# ASCII_06_LMS7002M_RF2.net
KiCad netlist of a schematic drawn in Altium Designer
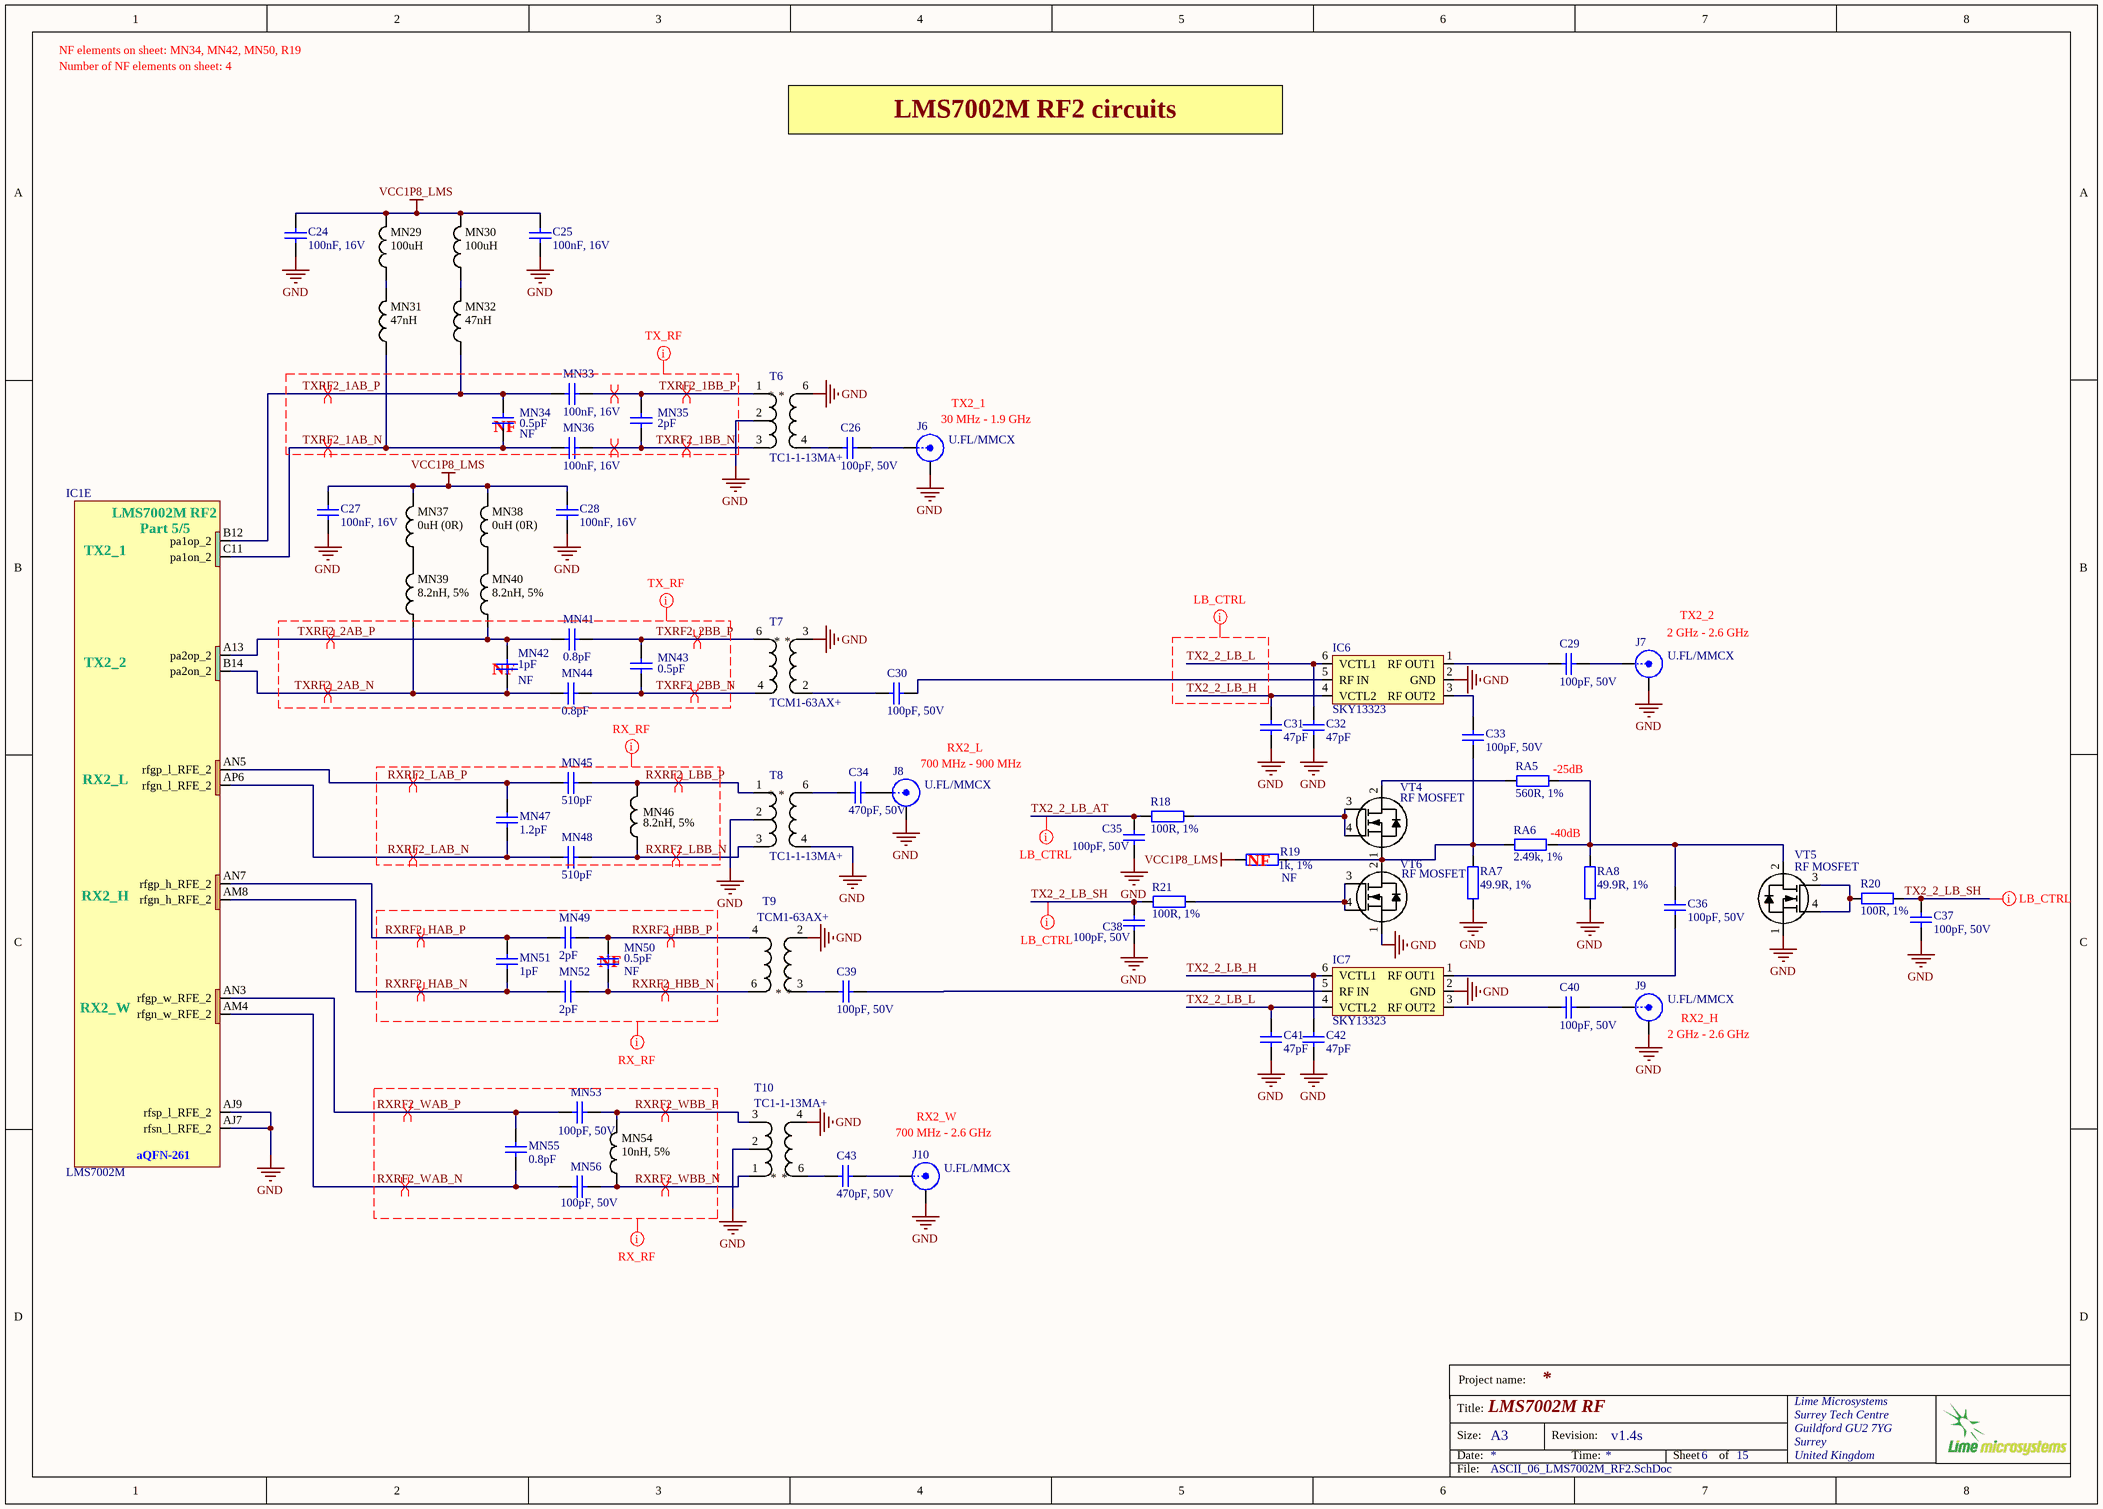
[diagram p0: ASCII_06_LMS7002M_RF2.SchDoc]

(export (version "E")
  (design (tool "Eeschema 10.0.6"))
  (components
    (comp (ref "C24")
      (value "100nF, 16V")
      (footprint "CAP0402")
      (fields
        (field (name "MANUFACTURER") "Murata Electronics")
        (field (name "TOLERANCE") "10 %")
        (field (name "MANUFACTURER PART NUMBER") "GRM155R71C104KA88D")
      )
      (libsource (lib "LimeMicroAltiumLib_schLib") (part "Cap_0402"))
    )
    (comp (ref "C25")
      (value "100nF, 16V")
      (footprint "CAP0402")
      (fields
        (field (name "MANUFACTURER") "Murata Electronics")
        (field (name "TOLERANCE") "10 %")
        (field (name "MANUFACTURER PART NUMBER") "GRM155R71C104KA88D")
      )
      (libsource (lib "LimeMicroAltiumLib_schLib") (part "Cap_0402"))
    )
    (comp (ref "C26")
      (value "100pF, 50V")
      (footprint "CAP0402")
      (fields (field (name "TOLERANCE") "±5%") (field (name "MANUFACTURER") "Yageo"))
      (libsource (lib "LimeMicroAltiumLib_schLib") (part "Cap_0402"))
    )
    (comp (ref "C27")
      (value "100nF, 16V")
      (footprint "CAP0402")
      (fields
        (field (name "MANUFACTURER") "Murata Electronics")
        (field (name "TOLERANCE") "10 %")
        (field (name "MANUFACTURER PART NUMBER") "GRM155R71C104KA88D")
      )
      (libsource (lib "LimeMicroAltiumLib_schLib") (part "Cap_0402"))
    )
    (comp (ref "C28")
      (value "100nF, 16V")
      (footprint "CAP0402")
      (fields
        (field (name "MANUFACTURER") "Murata Electronics")
        (field (name "TOLERANCE") "10 %")
        (field (name "MANUFACTURER PART NUMBER") "GRM155R71C104KA88D")
      )
      (libsource (lib "LimeMicroAltiumLib_schLib") (part "Cap_0402"))
    )
    (comp (ref "C29")
      (value "100pF, 50V")
      (footprint "CAP0402")
      (fields (field (name "TOLERANCE") "±5%") (field (name "MANUFACTURER") "Yageo"))
      (libsource (lib "LimeMicroAltiumLib_schLib") (part "Cap_0402"))
    )
    (comp (ref "C30")
      (value "100pF, 50V")
      (footprint "CAP0402")
      (fields (field (name "TOLERANCE") "±5%") (field (name "MANUFACTURER") "Yageo"))
      (libsource (lib "LimeMicroAltiumLib_schLib") (part "Cap_0402"))
    )
    (comp (ref "C31")
      (value "47pF")
      (footprint "CAP0402")
      (fields (field (name "TOLERANCE") "±1%") (field (name "MANUFACTURER") "TDK Corporation"))
      (libsource (lib "LimeMicroAltiumLib_schLib") (part "Cap_0402"))
    )
    (comp (ref "C32")
      (value "47pF")
      (footprint "CAP0402")
      (fields (field (name "TOLERANCE") "±1%") (field (name "MANUFACTURER") "TDK Corporation"))
      (libsource (lib "LimeMicroAltiumLib_schLib") (part "Cap_0402"))
    )
    (comp (ref "C33")
      (value "100pF, 50V")
      (footprint "CAP0402")
      (fields (field (name "TOLERANCE") "±5%") (field (name "MANUFACTURER") "Yageo"))
      (libsource (lib "LimeMicroAltiumLib_schLib") (part "Cap_0402"))
    )
    (comp (ref "C34")
      (value "470pF, 50V")
      (footprint "CAP0402")
      (fields
        (field (name "MANUFACTURER PART NUMBER") "C1005C0G1H471J050BA")
        (field (name "TOLERANCE") "±5%")
        (field (name "MANUFACTURER") "TDK Corporation")
      )
      (libsource (lib "LimeMicroAltiumLib_schLib") (part "Cap_0402"))
    )
    (comp (ref "C35")
      (value "100pF, 50V")
      (footprint "CAP0402")
      (fields (field (name "TOLERANCE") "±5%") (field (name "MANUFACTURER") "Yageo"))
      (libsource (lib "LimeMicroAltiumLib_schLib") (part "Cap_0402"))
    )
    (comp (ref "C36")
      (value "100pF, 50V")
      (footprint "CAP0402")
      (fields (field (name "TOLERANCE") "±5%") (field (name "MANUFACTURER") "Yageo"))
      (libsource (lib "LimeMicroAltiumLib_schLib") (part "Cap_0402"))
    )
    (comp (ref "C37")
      (value "100pF, 50V")
      (footprint "CAP0402")
      (fields (field (name "TOLERANCE") "±5%") (field (name "MANUFACTURER") "Yageo"))
      (libsource (lib "LimeMicroAltiumLib_schLib") (part "Cap_0402"))
    )
    (comp (ref "C38")
      (value "100pF, 50V")
      (footprint "CAP0402")
      (fields (field (name "TOLERANCE") "±5%") (field (name "MANUFACTURER") "Yageo"))
      (libsource (lib "LimeMicroAltiumLib_schLib") (part "Cap_0402"))
    )
    (comp (ref "C39")
      (value "100pF, 50V")
      (footprint "CAP0402")
      (fields (field (name "TOLERANCE") "±5%") (field (name "MANUFACTURER") "Yageo"))
      (libsource (lib "LimeMicroAltiumLib_schLib") (part "Cap_0402"))
    )
    (comp (ref "C40")
      (value "100pF, 50V")
      (footprint "CAP0402")
      (fields (field (name "TOLERANCE") "±5%") (field (name "MANUFACTURER") "Yageo"))
      (libsource (lib "LimeMicroAltiumLib_schLib") (part "Cap_0402"))
    )
    (comp (ref "C41")
      (value "47pF")
      (footprint "CAP0402")
      (fields (field (name "TOLERANCE") "±1%") (field (name "MANUFACTURER") "TDK Corporation"))
      (libsource (lib "LimeMicroAltiumLib_schLib") (part "Cap_0402"))
    )
    (comp (ref "C42")
      (value "47pF")
      (footprint "CAP0402")
      (fields (field (name "TOLERANCE") "±1%") (field (name "MANUFACTURER") "TDK Corporation"))
      (libsource (lib "LimeMicroAltiumLib_schLib") (part "Cap_0402"))
    )
    (comp (ref "C43")
      (value "470pF, 50V")
      (footprint "CAP0402")
      (fields
        (field (name "MANUFACTURER PART NUMBER") "C1005C0G1H471J050BA")
        (field (name "TOLERANCE") "±5%")
        (field (name "MANUFACTURER") "TDK Corporation")
      )
      (libsource (lib "LimeMicroAltiumLib_schLib") (part "Cap_0402"))
    )
    (comp (ref "IC1")
      (value "LMS7002M")
      (footprint "LMS7002M_v3")
      (fields (field (name "MANUFACTURER") "Lime Microsystems"))
      (libsource (lib "LimeMicroAltiumLib_schLib") (part "LMS7002M"))
    )
    (comp (ref "IC6")
      (value "SKY13323")
      (footprint "SKY13323-378LF")
      (description "SKY13323-378LF: 0.1-3.0 GHz GaAs SPDT Switch")
      (fields (field (name "MANUFACTURER") "Skyworks Solutions Inc."))
      (libsource (lib "LimeMicroAltiumLib_schLib") (part "SKY13323"))
    )
    (comp (ref "IC7")
      (value "SKY13323")
      (footprint "SKY13323-378LF")
      (description "SKY13323-378LF: 0.1-3.0 GHz GaAs SPDT Switch")
      (fields (field (name "MANUFACTURER") "Skyworks Solutions Inc."))
      (libsource (lib "LimeMicroAltiumLib_schLib") (part "SKY13323"))
    )
    (comp (ref "J6")
      (value "U.FL/MMCX")
      (footprint "MMCX_UFL_conn_u")
      (description "CONN UMC RCPT STR 50 OHM SMD")
      (fields (field (name "MANUFACTURER") "Molex, LLC"))
      (libsource (lib "LimeMicroAltiumLib_schLib") (part "RF_IF_connector"))
    )
    (comp (ref "J7")
      (value "U.FL/MMCX")
      (footprint "MMCX_UFL_conn_u")
      (description "CONN UMC RCPT STR 50 OHM SMD")
      (fields (field (name "MANUFACTURER") "Molex, LLC"))
      (libsource (lib "LimeMicroAltiumLib_schLib") (part "RF_IF_connector"))
    )
    (comp (ref "J8")
      (value "U.FL/MMCX")
      (footprint "MMCX_UFL_conn_u")
      (description "CONN UMC RCPT STR 50 OHM SMD")
      (fields (field (name "MANUFACTURER") "Molex, LLC"))
      (libsource (lib "LimeMicroAltiumLib_schLib") (part "RF_IF_connector"))
    )
    (comp (ref "J9")
      (value "U.FL/MMCX")
      (footprint "MMCX_UFL_conn_u")
      (description "CONN UMC RCPT STR 50 OHM SMD")
      (fields (field (name "MANUFACTURER") "Molex, LLC"))
      (libsource (lib "LimeMicroAltiumLib_schLib") (part "RF_IF_connector"))
    )
    (comp (ref "J10")
      (value "U.FL/MMCX")
      (footprint "MMCX_UFL_conn_u")
      (description "CONN UMC RCPT STR 50 OHM SMD")
      (fields (field (name "MANUFACTURER") "Molex, LLC"))
      (libsource (lib "LimeMicroAltiumLib_schLib") (part "RF_IF_connector"))
    )
    (comp (ref "MN29")
      (value "100uH")
      (footprint "RES0805")
      (fields
        (field (name "TOLERANCE") "±10%")
        (field (name "MANUFACTURER") "TDK Corporation")
        (field (name "MANUFACTURER PART NUMBER") "MLF2012C101KT000")
      )
      (libsource (lib "LimeMicroAltiumLib_schLib") (part "Inductor_0603"))
    )
    (comp (ref "MN30")
      (value "100uH")
      (footprint "RES0805")
      (fields
        (field (name "TOLERANCE") "±10%")
        (field (name "MANUFACTURER") "TDK Corporation")
        (field (name "MANUFACTURER PART NUMBER") "MLF2012C101KT000")
      )
      (libsource (lib "LimeMicroAltiumLib_schLib") (part "Inductor_0603"))
    )
    (comp (ref "MN31")
      (value "47nH")
      (footprint "RES0402")
      (fields
        (field (name "MANUFACTURER") "COILCRAFT")
        (field (name "MANUFACTURER PART NUMBER") "0402HP-47NXJLU")
      )
      (libsource (lib "LimeMicroAltiumLib_schLib") (part "Inductor_0603"))
    )
    (comp (ref "MN32")
      (value "47nH")
      (footprint "RES0402")
      (fields
        (field (name "MANUFACTURER") "COILCRAFT")
        (field (name "MANUFACTURER PART NUMBER") "0402HP-47NXJLU")
      )
      (libsource (lib "LimeMicroAltiumLib_schLib") (part "Inductor_0603"))
    )
    (comp (ref "MN33")
      (value "100nF, 16V")
      (footprint "CAP0402")
      (fields
        (field (name "MANUFACTURER") "Murata Electronics")
        (field (name "TOLERANCE") "10 %")
        (field (name "MANUFACTURER PART NUMBER") "GRM155R71C104KA88D")
      )
      (libsource (lib "LimeMicroAltiumLib_schLib") (part "Cap_0402"))
    )
    (comp (ref "MN34")
      (value "0.5pF")
      (footprint "CAP0402")
      (fields
        (field (name "ASSEMBLY INFO") "NF")
        (field (name "TOLERANCE") "±0.25pF")
        (field (name "MANUFACTURER") "Yageo")
      )
      (libsource (lib "LimeMicroAltiumLib_schLib") (part "Cap_0402"))
    )
    (comp (ref "MN35")
      (value "2pF")
      (footprint "CAP0402")
      (fields (field (name "MANUFACTURER PART NUMBER") "04025U2R0BAT2A") (field (name "MANUFACTURER") "AVX"))
      (libsource (lib "LimeMicroAltiumLib_schLib") (part "Cap_0402"))
    )
    (comp (ref "MN36")
      (value "100nF, 16V")
      (footprint "CAP0402")
      (fields
        (field (name "MANUFACTURER") "Murata Electronics")
        (field (name "TOLERANCE") "10 %")
        (field (name "MANUFACTURER PART NUMBER") "GRM155R71C104KA88D")
      )
      (libsource (lib "LimeMicroAltiumLib_schLib") (part "Cap_0402"))
    )
    (comp (ref "MN37")
      (value "0uH (0R)")
      (footprint "RES0805")
      (fields (field (name "MANUFACTURER") "BOURNS"))
      (libsource (lib "LimeMicroAltiumLib_schLib") (part "Inductor_0603"))
    )
    (comp (ref "MN38")
      (value "0uH (0R)")
      (footprint "RES0805")
      (fields (field (name "MANUFACTURER") "BOURNS"))
      (libsource (lib "LimeMicroAltiumLib_schLib") (part "Inductor_0603"))
    )
    (comp (ref "MN39")
      (value "8.2nH, 5%")
      (footprint "RES0402")
      (fields (field (name "MANUFACTURER") "COILCRAFT"))
      (libsource (lib "LimeMicroAltiumLib_schLib") (part "Inductor_0603"))
    )
    (comp (ref "MN40")
      (value "8.2nH, 5%")
      (footprint "RES0402")
      (fields (field (name "MANUFACTURER") "COILCRAFT"))
      (libsource (lib "LimeMicroAltiumLib_schLib") (part "Inductor_0603"))
    )
    (comp (ref "MN41")
      (value "0.8pF")
      (footprint "CAP0402")
      (fields
        (field (name "TOLERANCE") "±0.1pF")
        (field (name "MANUFACTURER") "Murata Electronics North America")
        (field (name "MANUFACTURER PART NUMBER") "GRM1555C1HR80BA01D")
      )
      (libsource (lib "LimeMicroAltiumLib_schLib") (part "Cap_0402"))
    )
    (comp (ref "MN42")
      (value "1pF")
      (footprint "CAP0402")
      (fields
        (field (name "ASSEMBLY INFO") "NF")
        (field (name "MANUFACTURER") "TDK Corporation")
        (field (name "TOLERANCE") "±0.1pF")
      )
      (libsource (lib "LimeMicroAltiumLib_schLib") (part "Cap_0402"))
    )
    (comp (ref "MN43")
      (value "0.5pF")
      (footprint "CAP0402")
      (fields (field (name "TOLERANCE") "±0.25pF") (field (name "MANUFACTURER") "Yageo"))
      (libsource (lib "LimeMicroAltiumLib_schLib") (part "Cap_0402"))
    )
    (comp (ref "MN44")
      (value "0.8pF")
      (footprint "CAP0402")
      (fields
        (field (name "TOLERANCE") "±0.1pF")
        (field (name "MANUFACTURER") "Murata Electronics North America")
        (field (name "MANUFACTURER PART NUMBER") "GRM1555C1HR80BA01D")
      )
      (libsource (lib "LimeMicroAltiumLib_schLib") (part "Cap_0402"))
    )
    (comp (ref "MN45")
      (value "510pF")
      (footprint "CAP0402")
      (fields
        (field (name "TOLERANCE") "±5%")
        (field (name "MANUFACTURER") "Murata Electronics North America")
        (field (name "MANUFACTURER PART NUMBER") "GRM1555C1H511JA01D")
      )
      (libsource (lib "LimeMicroAltiumLib_schLib") (part "Cap_0402"))
    )
    (comp (ref "MN46")
      (value "8.2nH, 5%")
      (footprint "RES0402")
      (fields (field (name "MANUFACTURER") "COILCRAFT"))
      (libsource (lib "LimeMicroAltiumLib_schLib") (part "Inductor_0603"))
    )
    (comp (ref "MN47")
      (value "1.2pF")
      (footprint "CAP0402")
      (fields
        (field (name "MANUFACTURER") "Murata Electronics North America")
        (field (name "MANUFACTURER PART NUMBER") "GRM1555C1H1R2CA01D")
        (field (name "TOLERANCE") "±0.25pF")
      )
      (libsource (lib "LimeMicroAltiumLib_schLib") (part "Cap_0402"))
    )
    (comp (ref "MN48")
      (value "510pF")
      (footprint "CAP0402")
      (fields
        (field (name "TOLERANCE") "±5%")
        (field (name "MANUFACTURER") "Murata Electronics North America")
        (field (name "MANUFACTURER PART NUMBER") "GRM1555C1H511JA01D")
      )
      (libsource (lib "LimeMicroAltiumLib_schLib") (part "Cap_0402"))
    )
    (comp (ref "MN49")
      (value "2pF")
      (footprint "CAP0402")
      (fields (field (name "MANUFACTURER PART NUMBER") "04025U2R0BAT2A") (field (name "MANUFACTURER") "AVX"))
      (libsource (lib "LimeMicroAltiumLib_schLib") (part "Cap_0402"))
    )
    (comp (ref "MN50")
      (value "0.5pF")
      (footprint "CAP0402")
      (fields
        (field (name "ASSEMBLY INFO") "NF")
        (field (name "TOLERANCE") "±0.25pF")
        (field (name "MANUFACTURER") "Yageo")
      )
      (libsource (lib "LimeMicroAltiumLib_schLib") (part "Cap_0402"))
    )
    (comp (ref "MN51")
      (value "1pF")
      (footprint "CAP0402")
      (fields (field (name "MANUFACTURER") "TDK Corporation") (field (name "TOLERANCE") "±0.1pF"))
      (libsource (lib "LimeMicroAltiumLib_schLib") (part "Cap_0402"))
    )
    (comp (ref "MN52")
      (value "2pF")
      (footprint "CAP0402")
      (fields (field (name "MANUFACTURER PART NUMBER") "04025U2R0BAT2A") (field (name "MANUFACTURER") "AVX"))
      (libsource (lib "LimeMicroAltiumLib_schLib") (part "Cap_0402"))
    )
    (comp (ref "MN53")
      (value "100pF, 50V")
      (footprint "CAP0402")
      (fields (field (name "TOLERANCE") "±5%") (field (name "MANUFACTURER") "Yageo"))
      (libsource (lib "LimeMicroAltiumLib_schLib") (part "Cap_0402"))
    )
    (comp (ref "MN54")
      (value "10nH, 5%")
      (footprint "RES0402")
      (fields (field (name "MANUFACTURER") "COILCRAFT"))
      (libsource (lib "LimeMicroAltiumLib_schLib") (part "Inductor_0603"))
    )
    (comp (ref "MN55")
      (value "0.8pF")
      (footprint "CAP0402")
      (fields
        (field (name "TOLERANCE") "±0.1pF")
        (field (name "MANUFACTURER") "Murata Electronics North America")
        (field (name "MANUFACTURER PART NUMBER") "GRM1555C1HR80BA01D")
      )
      (libsource (lib "LimeMicroAltiumLib_schLib") (part "Cap_0402"))
    )
    (comp (ref "MN56")
      (value "100pF, 50V")
      (footprint "CAP0402")
      (fields (field (name "TOLERANCE") "±5%") (field (name "MANUFACTURER") "Yageo"))
      (libsource (lib "LimeMicroAltiumLib_schLib") (part "Cap_0402"))
    )
    (comp (ref "R18")
      (value "100R, 1%")
      (footprint "RES0402")
      (fields (field (name "TOLERANCE") "±1%") (field (name "MANUFACTURER") "Stackpole Electronics Inc."))
      (libsource (lib "LimeFPGAboard_schLib") (part "Res_0402"))
    )
    (comp (ref "R19")
      (value "1k, 1%")
      (footprint "RES0402")
      (fields
        (field (name "ASSEMBLY INFO") "NF")
        (field (name "MANUFACTURER") "Stackpole Electronics Inc")
        (field (name "TOLERANCE") "±1%")
      )
      (libsource (lib "LimeMicroAltiumLib_schLib") (part "Res_0402"))
    )
    (comp (ref "R20")
      (value "100R, 1%")
      (footprint "RES0402")
      (fields (field (name "TOLERANCE") "±1%") (field (name "MANUFACTURER") "Stackpole Electronics Inc."))
      (libsource (lib "LimeFPGAboard_schLib") (part "Res_0402"))
    )
    (comp (ref "R21")
      (value "100R, 1%")
      (footprint "RES0402")
      (fields (field (name "TOLERANCE") "±1%") (field (name "MANUFACTURER") "Stackpole Electronics Inc."))
      (libsource (lib "LimeFPGAboard_schLib") (part "Res_0402"))
    )
    (comp (ref "RA5")
      (value "560R, 1%")
      (footprint "RES0402")
      (fields
        (field (name "MANUFACTURER PART NUMBER") "CRCW0402560RFKED")
        (field (name "TOLERANCE") "±1%")
        (field (name "MANUFACTURER") "Vishay Dale")
      )
      (libsource (lib "LimeMicroAltiumLib_schLib") (part "Res_0402"))
    )
    (comp (ref "RA6")
      (value "2.49k, 1%")
      (footprint "RES0402")
      (fields
        (field (name "TOLERANCE") "±1%")
        (field (name "MANUFACTURER PART NUMBER") "RC0402FR-072K49L")
        (field (name "MANUFACTURER") "Yageo")
      )
      (libsource (lib "LimeMicroAltiumLib_schLib") (part "Res_0402"))
    )
    (comp (ref "RA7")
      (value "49.9R, 1%")
      (footprint "RES0402")
      (fields
        (field (name "TOLERANCE") "±1%")
        (field (name "MANUFACTURER") "Samsung Electro-Mechanics America, Inc.")
        (field (name "MANUFACTURER PART NUMBER") "RC1005F49R9CS")
      )
      (libsource (lib "LimeMicroAltiumLib_schLib") (part "Res_0402"))
    )
    (comp (ref "RA8")
      (value "49.9R, 1%")
      (footprint "RES0402")
      (fields
        (field (name "TOLERANCE") "±1%")
        (field (name "MANUFACTURER") "Samsung Electro-Mechanics America, Inc.")
        (field (name "MANUFACTURER PART NUMBER") "RC1005F49R9CS")
      )
      (libsource (lib "LimeMicroAltiumLib_schLib") (part "Res_0402"))
    )
    (comp (ref "T6")
      (value "TC1-1-13MA+")
      (footprint "TC1-1-13MA+_v2")
      (fields (field (name "MANUFACTURER") "Mini-Circuits"))
      (libsource (lib "LimeMicroAltiumLib_schLib") (part "Balun"))
    )
    (comp (ref "T7")
      (value "TCM1-63AX+")
      (footprint "TCM1-63AX+_v2")
      (fields (field (name "MANUFACTURER") "Mini-circuits"))
      (libsource (lib "") (part "Balun_v2_1"))
    )
    (comp (ref "T8")
      (value "TC1-1-13MA+")
      (footprint "TC1-1-13MA+_v2")
      (fields (field (name "MANUFACTURER") "Mini-Circuits"))
      (libsource (lib "LimeMicroAltiumLib_schLib") (part "Balun"))
    )
    (comp (ref "T9")
      (value "TCM1-63AX+")
      (footprint "TCM1-63AX+_v2")
      (fields (field (name "MANUFACTURER") "Mini-circuits"))
      (libsource (lib "LimeMicroAltiumLib_schLib") (part "Balun_v2"))
    )
    (comp (ref "T10")
      (value "TC1-1-13MA+")
      (footprint "TC1-1-13MA+_v2")
      (fields (field (name "MANUFACTURER") "Mini-Circuits"))
      (libsource (lib "") (part "Balun_1"))
    )
    (comp (ref "VT4")
      (value "RF MOSFET")
      (footprint "BF1105R_SOT143R4")
      (fields (field (name "MANUFACTURER") "NXP Semiconductors"))
      (libsource (lib "LimeMicroAltiumLib_schLib") (part "BF1105R,215"))
    )
    (comp (ref "VT5")
      (value "RF MOSFET")
      (footprint "BF1105R_SOT143R4")
      (fields (field (name "MANUFACTURER") "NXP Semiconductors"))
      (libsource (lib "LimeMicroAltiumLib_schLib") (part "BF1105R,215"))
    )
    (comp (ref "VT6")
      (value "RF MOSFET")
      (footprint "BF1105R_SOT143R4")
      (fields (field (name "MANUFACTURER") "NXP Semiconductors"))
      (libsource (lib "LimeMicroAltiumLib_schLib") (part "BF1105R,215"))
    )
  )
  (nets
    (net (code "1") (name "/RXRF2_HAB_N") (class "Default")
      (node (ref "IC1") (pin "AM8") (pinfunction "rfgn_h_RFE_2_AM8") (pintype "passive"))
      (node (ref "MN51") (pin "1") (pinfunction "1_1") (pintype "passive"))
      (node (ref "MN52") (pin "2") (pinfunction "2_2") (pintype "passive"))
    )
    (net (code "2") (name "/RXRF2_HAB_P") (class "Default")
      (node (ref "IC1") (pin "AN7") (pinfunction "rfgp_h_RFE_2_AN7") (pintype "passive"))
      (node (ref "MN49") (pin "2") (pinfunction "2_2") (pintype "passive"))
      (node (ref "MN51") (pin "2") (pinfunction "2_2") (pintype "passive"))
    )
    (net (code "3") (name "/RXRF2_HBB_N") (class "Default")
      (node (ref "MN50") (pin "1") (pinfunction "1_1") (pintype "passive"))
      (node (ref "MN52") (pin "1") (pinfunction "1_1") (pintype "passive"))
      (node (ref "T9") (pin "6") (pinfunction "6_6") (pintype "passive"))
    )
    (net (code "4") (name "/RXRF2_HBB_P") (class "Default")
      (node (ref "MN49") (pin "1") (pinfunction "1_1") (pintype "passive"))
      (node (ref "MN50") (pin "2") (pinfunction "2_2") (pintype "passive"))
      (node (ref "T9") (pin "4") (pinfunction "4_4") (pintype "passive"))
    )
    (net (code "5") (name "/RXRF2_LAB_N") (class "Default")
      (node (ref "IC1") (pin "AP6") (pinfunction "rfgn_l_RFE_2_AP6") (pintype "passive"))
      (node (ref "MN47") (pin "1") (pinfunction "1_1") (pintype "passive"))
      (node (ref "MN48") (pin "2") (pinfunction "2_2") (pintype "passive"))
    )
    (net (code "6") (name "/RXRF2_LAB_P") (class "Default")
      (node (ref "IC1") (pin "AN5") (pinfunction "rfgp_l_RFE_2_AN5") (pintype "passive"))
      (node (ref "MN45") (pin "2") (pinfunction "2_2") (pintype "passive"))
      (node (ref "MN47") (pin "2") (pinfunction "2_2") (pintype "passive"))
    )
    (net (code "7") (name "/RXRF2_LBB_N") (class "Default")
      (node (ref "MN46") (pin "1") (pinfunction "1_1") (pintype "passive"))
      (node (ref "MN48") (pin "1") (pinfunction "1_1") (pintype "passive"))
      (node (ref "T8") (pin "3") (pinfunction "3_3") (pintype "passive"))
    )
    (net (code "8") (name "/RXRF2_LBB_P") (class "Default")
      (node (ref "MN45") (pin "1") (pinfunction "1_1") (pintype "passive"))
      (node (ref "MN46") (pin "2") (pinfunction "2_2") (pintype "passive"))
      (node (ref "T8") (pin "1") (pinfunction "1_1") (pintype "passive"))
    )
    (net (code "9") (name "/RXRF2_WAB_N") (class "Default")
      (node (ref "IC1") (pin "AM4") (pinfunction "rfgn_w_RFE_2_AM4") (pintype "passive"))
      (node (ref "MN55") (pin "2") (pinfunction "2_2") (pintype "passive"))
      (node (ref "MN56") (pin "2") (pinfunction "2_2") (pintype "passive"))
    )
    (net (code "10") (name "/RXRF2_WAB_P") (class "Default")
      (node (ref "IC1") (pin "AN3") (pinfunction "rfgp_w_RFE_2_AN3") (pintype "passive"))
      (node (ref "MN53") (pin "2") (pinfunction "2_2") (pintype "passive"))
      (node (ref "MN55") (pin "1") (pinfunction "1_1") (pintype "passive"))
    )
    (net (code "11") (name "/RXRF2_WBB_N") (class "Default")
      (node (ref "MN54") (pin "1") (pinfunction "1_1") (pintype "passive"))
      (node (ref "MN56") (pin "1") (pinfunction "1_1") (pintype "passive"))
      (node (ref "T10") (pin "1") (pinfunction "1_1") (pintype "passive"))
    )
    (net (code "12") (name "/RXRF2_WBB_P") (class "Default")
      (node (ref "MN53") (pin "1") (pinfunction "1_1") (pintype "passive"))
      (node (ref "MN54") (pin "2") (pinfunction "2_2") (pintype "passive"))
      (node (ref "T10") (pin "3") (pinfunction "3_3") (pintype "passive"))
    )
    (net (code "13") (name "/TX2_2_LB_AT") (class "Default")
      (node (ref "C35") (pin "1") (pinfunction "1_1") (pintype "passive"))
      (node (ref "R18") (pin "2") (pinfunction "2_2") (pintype "passive"))
    )
    (net (code "14") (name "/TX2_2_LB_H") (class "Default")
      (node (ref "C31") (pin "2") (pinfunction "2_2") (pintype "passive"))
      (node (ref "C42") (pin "2") (pinfunction "2_2") (pintype "passive"))
      (node (ref "IC6") (pin "4") (pinfunction "VCTL2_4") (pintype "input"))
      (node (ref "IC7") (pin "6") (pinfunction "VCTL1_6") (pintype "input"))
    )
    (net (code "15") (name "/TX2_2_LB_L") (class "Default")
      (node (ref "C32") (pin "2") (pinfunction "2_2") (pintype "passive"))
      (node (ref "C41") (pin "2") (pinfunction "2_2") (pintype "passive"))
      (node (ref "IC6") (pin "6") (pinfunction "VCTL1_6") (pintype "input"))
      (node (ref "IC7") (pin "4") (pinfunction "VCTL2_4") (pintype "input"))
    )
    (net (code "16") (name "/TX2_2_LB_SH") (class "Default")
      (node (ref "C37") (pin "1") (pinfunction "1_1") (pintype "passive"))
      (node (ref "C38") (pin "1") (pinfunction "1_1") (pintype "passive"))
      (node (ref "R20") (pin "1") (pinfunction "1_1") (pintype "passive"))
      (node (ref "R21") (pin "2") (pinfunction "2_2") (pintype "passive"))
    )
    (net (code "17") (name "/TXRF2_1AB_N") (class "Default")
      (node (ref "IC1") (pin "C11") (pinfunction "pa1on_2_C11") (pintype "passive"))
      (node (ref "MN31") (pin "1") (pinfunction "1_1") (pintype "passive"))
      (node (ref "MN34") (pin "1") (pinfunction "1_1") (pintype "passive"))
      (node (ref "MN36") (pin "1") (pinfunction "1_1") (pintype "passive"))
    )
    (net (code "18") (name "/TXRF2_1AB_P") (class "Default")
      (node (ref "IC1") (pin "B12") (pinfunction "pa1op_2_B12") (pintype "passive"))
      (node (ref "MN32") (pin "1") (pinfunction "1_1") (pintype "passive"))
      (node (ref "MN33") (pin "2") (pinfunction "2_2") (pintype "passive"))
      (node (ref "MN34") (pin "2") (pinfunction "2_2") (pintype "passive"))
    )
    (net (code "19") (name "/TXRF2_1BB_N") (class "Default")
      (node (ref "MN35") (pin "1") (pinfunction "1_1") (pintype "passive"))
      (node (ref "MN36") (pin "2") (pinfunction "2_2") (pintype "passive"))
      (node (ref "T6") (pin "3") (pinfunction "3_3") (pintype "passive"))
    )
    (net (code "20") (name "/TXRF2_1BB_P") (class "Default")
      (node (ref "MN33") (pin "1") (pinfunction "1_1") (pintype "passive"))
      (node (ref "MN35") (pin "2") (pinfunction "2_2") (pintype "passive"))
      (node (ref "T6") (pin "1") (pinfunction "1_1") (pintype "passive"))
    )
    (net (code "21") (name "/TXRF2_2AB_N") (class "Default")
      (node (ref "IC1") (pin "B14") (pinfunction "pa2on_2_B14") (pintype "passive"))
      (node (ref "MN39") (pin "1") (pinfunction "1_1") (pintype "passive"))
      (node (ref "MN42") (pin "2") (pinfunction "2_2") (pintype "passive"))
      (node (ref "MN44") (pin "2") (pinfunction "2_2") (pintype "passive"))
    )
    (net (code "22") (name "/TXRF2_2AB_P") (class "Default")
      (node (ref "IC1") (pin "A13") (pinfunction "pa2op_2_A13") (pintype "passive"))
      (node (ref "MN40") (pin "1") (pinfunction "1_1") (pintype "passive"))
      (node (ref "MN41") (pin "2") (pinfunction "2_2") (pintype "passive"))
      (node (ref "MN42") (pin "1") (pinfunction "1_1") (pintype "passive"))
    )
    (net (code "23") (name "/TXRF2_2BB_N") (class "Default")
      (node (ref "MN43") (pin "1") (pinfunction "1_1") (pintype "passive"))
      (node (ref "MN44") (pin "1") (pinfunction "1_1") (pintype "passive"))
      (node (ref "T7") (pin "4") (pinfunction "4_4") (pintype "passive"))
    )
    (net (code "24") (name "/TXRF2_2BB_P") (class "Default")
      (node (ref "MN41") (pin "1") (pinfunction "1_1") (pintype "passive"))
      (node (ref "MN43") (pin "2") (pinfunction "2_2") (pintype "passive"))
      (node (ref "T7") (pin "6") (pinfunction "6_6") (pintype "passive"))
    )
    (net (code "25") (name "GND") (class "Default")
      (node (ref "C24") (pin "1") (pinfunction "1_1") (pintype "passive"))
      (node (ref "C25") (pin "1") (pinfunction "1_1") (pintype "passive"))
      (node (ref "C27") (pin "1") (pinfunction "1_1") (pintype "passive"))
      (node (ref "C28") (pin "1") (pinfunction "1_1") (pintype "passive"))
      (node (ref "C31") (pin "1") (pinfunction "1_1") (pintype "passive"))
      (node (ref "C32") (pin "1") (pinfunction "1_1") (pintype "passive"))
      (node (ref "C35") (pin "2") (pinfunction "2_2") (pintype "passive"))
      (node (ref "C37") (pin "2") (pinfunction "2_2") (pintype "passive"))
      (node (ref "C38") (pin "2") (pinfunction "2_2") (pintype "passive"))
      (node (ref "C41") (pin "1") (pinfunction "1_1") (pintype "passive"))
      (node (ref "C42") (pin "1") (pinfunction "1_1") (pintype "passive"))
      (node (ref "IC1") (pin "AJ7") (pinfunction "rfsn_l_RFE_2_AJ7") (pintype "passive"))
      (node (ref "IC1") (pin "AJ9") (pinfunction "rfsp_l_RFE_2_AJ9") (pintype "passive"))
      (node (ref "IC6") (pin "2") (pinfunction "GND_2") (pintype "passive"))
      (node (ref "IC7") (pin "2") (pinfunction "GND_2") (pintype "passive"))
      (node (ref "J10") (pin "2") (pinfunction "Y_2") (pintype "passive"))
      (node (ref "J6") (pin "2") (pinfunction "Y_2") (pintype "passive"))
      (node (ref "J7") (pin "2") (pinfunction "Y_2") (pintype "passive"))
      (node (ref "J8") (pin "2") (pinfunction "Y_2") (pintype "passive"))
      (node (ref "J9") (pin "2") (pinfunction "Y_2") (pintype "passive"))
      (node (ref "RA7") (pin "1") (pinfunction "1_1") (pintype "passive"))
      (node (ref "RA8") (pin "1") (pinfunction "1_1") (pintype "passive"))
      (node (ref "T10") (pin "2") (pinfunction "2_2") (pintype "passive"))
      (node (ref "T10") (pin "4") (pinfunction "4_4") (pintype "passive"))
      (node (ref "T6") (pin "2") (pinfunction "2_2") (pintype "passive"))
      (node (ref "T6") (pin "6") (pinfunction "6_6") (pintype "passive"))
      (node (ref "T7") (pin "3") (pinfunction "3_3") (pintype "passive"))
      (node (ref "T8") (pin "2") (pinfunction "2_2") (pintype "passive"))
      (node (ref "T8") (pin "4") (pinfunction "4_4") (pintype "passive"))
      (node (ref "T9") (pin "2") (pinfunction "2_2") (pintype "passive"))
      (node (ref "VT5") (pin "1") (pinfunction "S_1") (pintype "passive"))
      (node (ref "VT6") (pin "1") (pinfunction "S_1") (pintype "passive"))
    )
    (net (code "26") (name "Net-(C26-Pad2)") (class "Default")
      (node (ref "C26") (pin "2") (pinfunction "2_2") (pintype "passive"))
      (node (ref "T6") (pin "4") (pinfunction "4_4") (pintype "passive"))
    )
    (net (code "27") (name "Net-(C30-Pad2)") (class "Default")
      (node (ref "C30") (pin "2") (pinfunction "2_2") (pintype "passive"))
      (node (ref "T7") (pin "2") (pinfunction "2_2") (pintype "passive"))
    )
    (net (code "28") (name "Net-(C34-Pad2)") (class "Default")
      (node (ref "C34") (pin "2") (pinfunction "2_2") (pintype "passive"))
      (node (ref "T8") (pin "6") (pinfunction "6_6") (pintype "passive"))
    )
    (net (code "29") (name "Net-(C39-Pad2)") (class "Default")
      (node (ref "C39") (pin "2") (pinfunction "2_2") (pintype "passive"))
      (node (ref "T9") (pin "3") (pinfunction "3_3") (pintype "passive"))
    )
    (net (code "30") (name "Net-(C43-Pad2)") (class "Default")
      (node (ref "C43") (pin "2") (pinfunction "2_2") (pintype "passive"))
      (node (ref "T10") (pin "6") (pinfunction "6_6") (pintype "passive"))
    )
    (net (code "31") (name "Net-(IC6-RF_IN)") (class "Default")
      (node (ref "C30") (pin "1") (pinfunction "1_1") (pintype "passive"))
      (node (ref "IC6") (pin "5") (pinfunction "RF_IN_5") (pintype "input"))
    )
    (net (code "32") (name "Net-(IC6-RF_OUT1)") (class "Default")
      (node (ref "C29") (pin "2") (pinfunction "2_2") (pintype "passive"))
      (node (ref "IC6") (pin "1") (pinfunction "RF_OUT1_1") (pintype "output"))
    )
    (net (code "33") (name "Net-(IC6-RF_OUT2)") (class "Default")
      (node (ref "C33") (pin "1") (pinfunction "1_1") (pintype "passive"))
      (node (ref "IC6") (pin "3") (pinfunction "RF_OUT2_3") (pintype "output"))
    )
    (net (code "34") (name "Net-(IC7-RF_IN)") (class "Default")
      (node (ref "C39") (pin "1") (pinfunction "1_1") (pintype "passive"))
      (node (ref "IC7") (pin "5") (pinfunction "RF_IN_5") (pintype "input"))
    )
    (net (code "35") (name "Net-(IC7-RF_OUT1)") (class "Default")
      (node (ref "C36") (pin "2") (pinfunction "2_2") (pintype "passive"))
      (node (ref "IC7") (pin "1") (pinfunction "RF_OUT1_1") (pintype "output"))
    )
    (net (code "36") (name "Net-(IC7-RF_OUT2)") (class "Default")
      (node (ref "C40") (pin "2") (pinfunction "2_2") (pintype "passive"))
      (node (ref "IC7") (pin "3") (pinfunction "RF_OUT2_3") (pintype "output"))
    )
    (net (code "37") (name "Net-(J6-X)") (class "Default")
      (node (ref "C26") (pin "1") (pinfunction "1_1") (pintype "passive"))
      (node (ref "J6") (pin "1") (pinfunction "X_1") (pintype "passive"))
    )
    (net (code "38") (name "Net-(J7-X)") (class "Default")
      (node (ref "C29") (pin "1") (pinfunction "1_1") (pintype "passive"))
      (node (ref "J7") (pin "1") (pinfunction "X_1") (pintype "passive"))
    )
    (net (code "39") (name "Net-(J8-X)") (class "Default")
      (node (ref "C34") (pin "1") (pinfunction "1_1") (pintype "passive"))
      (node (ref "J8") (pin "1") (pinfunction "X_1") (pintype "passive"))
    )
    (net (code "40") (name "Net-(J9-X)") (class "Default")
      (node (ref "C40") (pin "1") (pinfunction "1_1") (pintype "passive"))
      (node (ref "J9") (pin "1") (pinfunction "X_1") (pintype "passive"))
    )
    (net (code "41") (name "Net-(J10-X)") (class "Default")
      (node (ref "C43") (pin "1") (pinfunction "1_1") (pintype "passive"))
      (node (ref "J10") (pin "1") (pinfunction "X_1") (pintype "passive"))
    )
    (net (code "42") (name "Net-(MN29-Pad1)") (class "Default")
      (node (ref "MN29") (pin "1") (pinfunction "1_1") (pintype "passive"))
      (node (ref "MN31") (pin "2") (pinfunction "2_2") (pintype "passive"))
    )
    (net (code "43") (name "Net-(MN30-Pad1)") (class "Default")
      (node (ref "MN30") (pin "1") (pinfunction "1_1") (pintype "passive"))
      (node (ref "MN32") (pin "2") (pinfunction "2_2") (pintype "passive"))
    )
    (net (code "44") (name "Net-(MN37-Pad1)") (class "Default")
      (node (ref "MN37") (pin "1") (pinfunction "1_1") (pintype "passive"))
      (node (ref "MN39") (pin "2") (pinfunction "2_2") (pintype "passive"))
    )
    (net (code "45") (name "Net-(MN38-Pad1)") (class "Default")
      (node (ref "MN38") (pin "1") (pinfunction "1_1") (pintype "passive"))
      (node (ref "MN40") (pin "2") (pinfunction "2_2") (pintype "passive"))
    )
    (net (code "46") (name "Net-(VT4-D)") (class "Default")
      (node (ref "RA5") (pin "2") (pinfunction "2_2") (pintype "passive"))
      (node (ref "VT4") (pin "2") (pinfunction "D_2") (pintype "passive"))
    )
    (net (code "47") (name "Net-(VT4-G1)") (class "Default")
      (node (ref "R18") (pin "1") (pinfunction "1_1") (pintype "passive"))
      (node (ref "VT4") (pin "3") (pinfunction "G2_3") (pintype "passive"))
      (node (ref "VT4") (pin "4") (pinfunction "G1_4") (pintype "passive"))
    )
    (net (code "48") (name "Net-(VT4-S)") (class "Default")
      (node (ref "C33") (pin "2") (pinfunction "2_2") (pintype "passive"))
      (node (ref "R19") (pin "1") (pinfunction "1_1") (pintype "passive"))
      (node (ref "RA6") (pin "1") (pinfunction "1_1") (pintype "passive"))
      (node (ref "RA7") (pin "2") (pinfunction "2_2") (pintype "passive"))
      (node (ref "VT4") (pin "1") (pinfunction "S_1") (pintype "passive"))
      (node (ref "VT6") (pin "2") (pinfunction "D_2") (pintype "passive"))
    )
    (net (code "49") (name "Net-(VT5-D)") (class "Default")
      (node (ref "C36") (pin "1") (pinfunction "1_1") (pintype "passive"))
      (node (ref "RA5") (pin "1") (pinfunction "1_1") (pintype "passive"))
      (node (ref "RA6") (pin "2") (pinfunction "2_2") (pintype "passive"))
      (node (ref "RA8") (pin "2") (pinfunction "2_2") (pintype "passive"))
      (node (ref "VT5") (pin "2") (pinfunction "D_2") (pintype "passive"))
    )
    (net (code "50") (name "Net-(VT5-G1)") (class "Default")
      (node (ref "R20") (pin "2") (pinfunction "2_2") (pintype "passive"))
      (node (ref "VT5") (pin "3") (pinfunction "G2_3") (pintype "passive"))
      (node (ref "VT5") (pin "4") (pinfunction "G1_4") (pintype "passive"))
    )
    (net (code "51") (name "Net-(VT6-G1)") (class "Default")
      (node (ref "R21") (pin "1") (pinfunction "1_1") (pintype "passive"))
      (node (ref "VT6") (pin "3") (pinfunction "G2_3") (pintype "passive"))
      (node (ref "VT6") (pin "4") (pinfunction "G1_4") (pintype "passive"))
    )
    (net (code "52") (name "VCC1P8_LMS") (class "Default")
      (node (ref "C24") (pin "2") (pinfunction "2_2") (pintype "passive"))
      (node (ref "C25") (pin "2") (pinfunction "2_2") (pintype "passive"))
      (node (ref "C27") (pin "2") (pinfunction "2_2") (pintype "passive"))
      (node (ref "C28") (pin "2") (pinfunction "2_2") (pintype "passive"))
      (node (ref "MN29") (pin "2") (pinfunction "2_2") (pintype "passive"))
      (node (ref "MN30") (pin "2") (pinfunction "2_2") (pintype "passive"))
      (node (ref "MN37") (pin "2") (pinfunction "2_2") (pintype "passive"))
      (node (ref "MN38") (pin "2") (pinfunction "2_2") (pintype "passive"))
      (node (ref "R19") (pin "2") (pinfunction "2_2") (pintype "passive"))
    )
  )
)
